# DHT11_SCH.net
KiCad netlist of a schematic drawn in Altium Designer
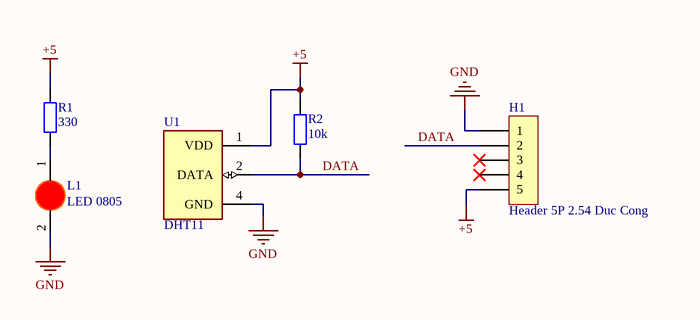
[diagram p0: DHT11_SCH.SchDoc]

(export (version "E")
  (design (tool "Eeschema 10.0.6"))
  (components
    (comp (ref "H1")
      (value "Header 5P 2.54 Duc Cong")
      (footprint "Header 5P DC 2.54")
      (description "Cắm")
      (libsource (lib "namnt_Lib") (part "Header 5P 2.54 Duc Cong"))
    )
    (comp (ref "L1")
      (value "LED 0805")
      (footprint "LED-0805-Red")
      (description "Dán")
      (libsource (lib "namnt_Lib") (part "LED 0805 Do"))
    )
    (comp (ref "R1")
      (value "330")
      (footprint "tro smd 0603")
      (description "Dán")
      (libsource (lib "namnt_Lib") (part "Tro 0603 1% 10k"))
    )
    (comp (ref "R2")
      (value "10k")
      (footprint "tro smd 0603")
      (description "Dán")
      (libsource (lib "namnt_Lib") (part "Tro 0603 1% 10k"))
    )
    (comp (ref "U1")
      (value "DHT11")
      (footprint "DHT11")
      (description "DHT11 basic temperature-humidity sensor + extras")
      (fields (field (name "MF") "Adafruit Industries") (field (name "MP") "ADA386"))
      (libsource (lib "namnt_Lib") (part "DHT11"))
    )
  )
  (nets
    (net (code "1") (name "+5") (class "Default")
      (node (ref "H1") (pin "5") (pinfunction "5_5") (pintype "passive"))
      (node (ref "R1") (pin "2") (pinfunction "2_2") (pintype "passive"))
      (node (ref "R2") (pin "2") (pinfunction "2_2") (pintype "passive"))
      (node (ref "U1") (pin "1") (pinfunction "VDD_1") (pintype "power_in"))
    )
    (net (code "2") (name "/DATA") (class "Default")
      (node (ref "H1") (pin "2") (pinfunction "2_2") (pintype "passive"))
      (node (ref "R2") (pin "1") (pinfunction "1_1") (pintype "passive"))
      (node (ref "U1") (pin "2") (pinfunction "DATA_2") (pintype "bidirectional"))
    )
    (net (code "3") (name "GND") (class "Default")
      (node (ref "H1") (pin "1") (pinfunction "1_1") (pintype "passive"))
      (node (ref "L1") (pin "2") (pinfunction "K_2") (pintype "passive"))
      (node (ref "U1") (pin "4") (pinfunction "GND_4") (pintype "power_in"))
    )
    (net (code "4") (name "Net-(L1-A)") (class "Default")
      (node (ref "L1") (pin "1") (pinfunction "A_1") (pintype "passive"))
      (node (ref "R1") (pin "1") (pinfunction "1_1") (pintype "passive"))
    )
    (net (code "5") (name "unconnected-(H1-Pad3)") (class "Default")
      (node (ref "H1") (pin "3") (pinfunction "3_3") (pintype "passive+no_connect"))
    )
    (net (code "6") (name "unconnected-(H1-Pad4)") (class "Default")
      (node (ref "H1") (pin "4") (pinfunction "4_4") (pintype "passive+no_connect"))
    )
  )
)
